# SCH_LoRaRice_Node__2024-06-10.net
KiCad netlist of a schematic drawn in EasyEDA
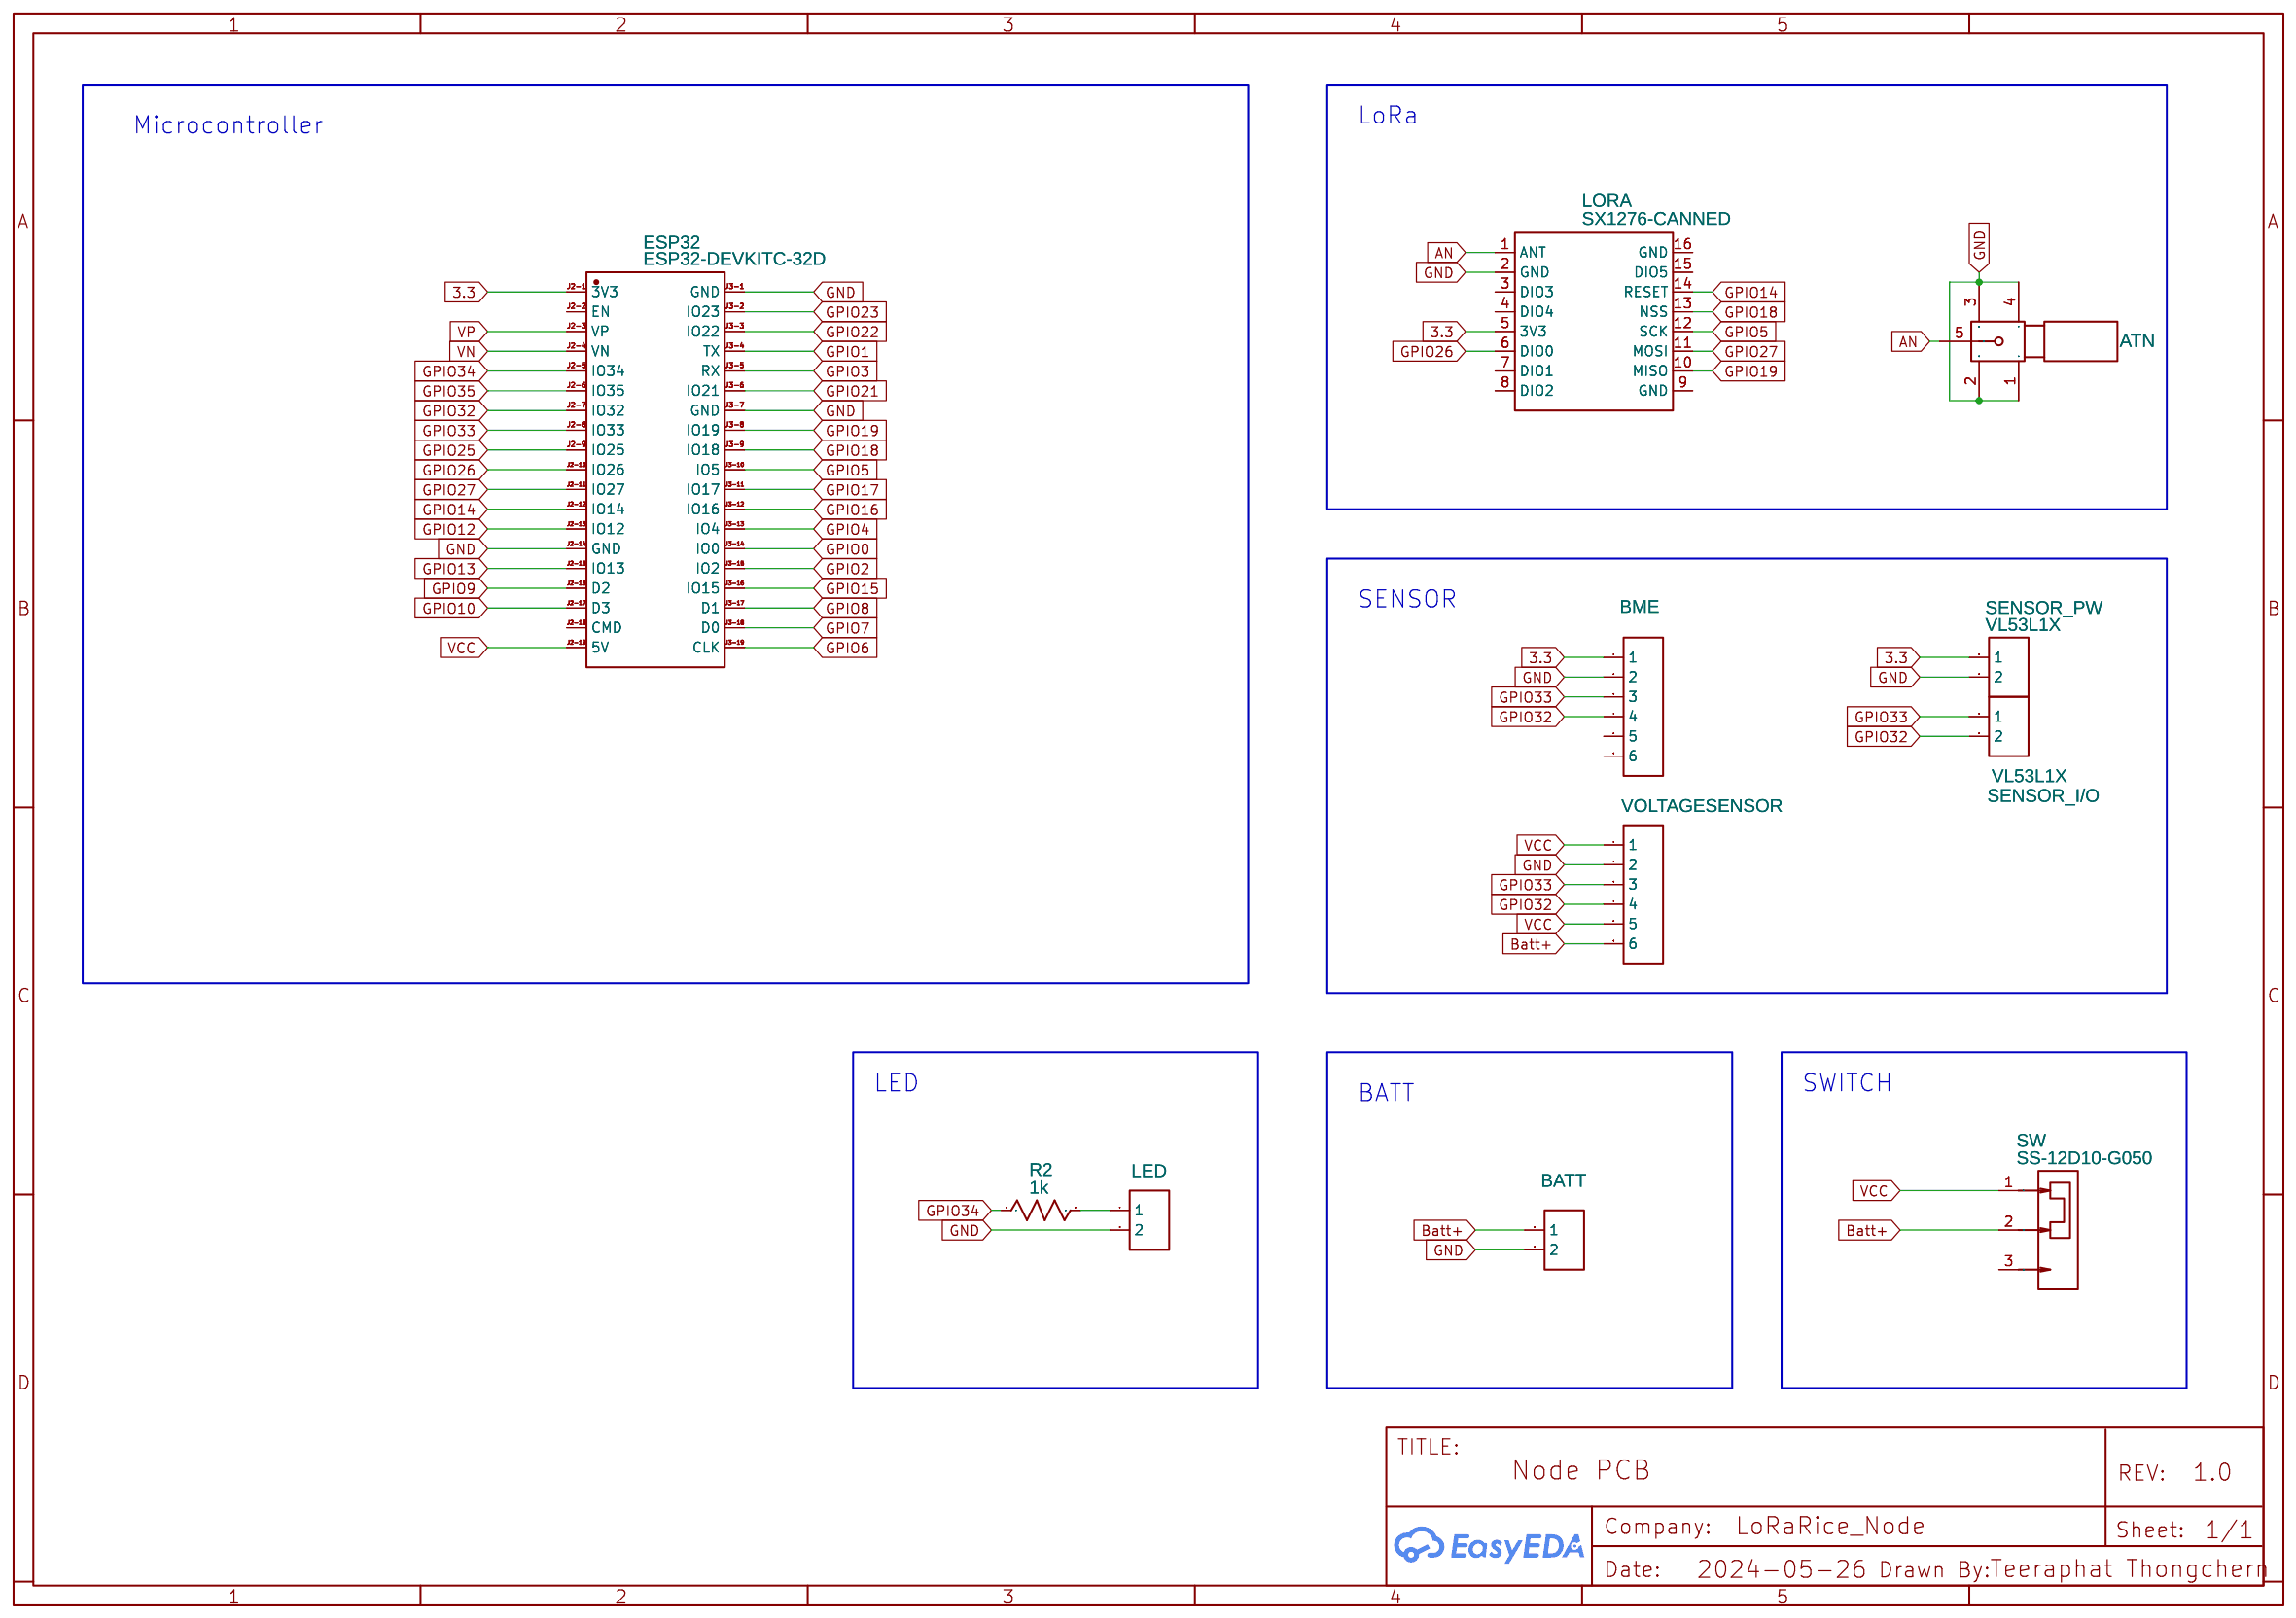
[diagram p0: schematic sheet]

(export (version "E")
  (design (tool "Eeschema 10.0.6"))
  (components
    (comp (ref "ATN")
      (value "ATN")
      (fields
        (field (name "Manufacturer Part") "BWSMA-KE-P001")
        (field (name "Manufacturer") "BAT WIRELESS(蝙蝠无线)")
      )
      (libsource (lib "") (part "BWSMA-KE-P001"))
    )
    (comp (ref "BATT") (value "VL53L1X") (libsource (lib "") (part "CONN-TH_2P-P5.00_1")))
    (comp (ref "BME") (value "00") (libsource (lib "") (part "HDR-F-2.54_1x6_1")))
    (comp (ref "ESP32")
      (value "ESP32-DEVKITC-32D")
      (fields
        (field (name "Manufacturer Part") "ESP32-DevKitC-32D")
        (field (name "Manufacturer") "ESPRESSIF(乐鑫)")
      )
      (libsource (lib "") (part "ESP32-DEVKITC-32D"))
    )
    (comp (ref "LED") (value "HDR-F-2.54_1x2") (libsource (lib "") (part "HDR-F-2.54_1x2")))
    (comp (ref "LORA")
      (value "SX1276-CANNED")
      (fields (field (name "Manufacturer Part") "LoRa1276-C1") (field (name "Manufacturer") "G-NiceRF"))
      (libsource (lib "") (part "SX1276-CANNED"))
    )
    (comp (ref "R2") (value "1k") (libsource (lib "") (part "R_AXIAL-0.4_US")))
    (comp (ref "SENSOR_I/O") (value "VL53L1X") (libsource (lib "") (part "CONN-TH_2P-P5.00")))
    (comp (ref "SENSOR_PW") (value "VL53L1X") (libsource (lib "") (part "CONN-TH_2P-P5.00_2")))
    (comp (ref "SW")
      (value "SS-12D10-G050")
      (fields (field (name "Manufacturer") "G-Switch(品赞)"))
      (libsource (lib "") (part "SS-12D10-G050"))
    )
    (comp (ref "VOLTAGESENSOR") (value "00") (libsource (lib "") (part "HDR-F-2.54_1x6")))
  )
  (nets
    (net (code "1") (name "3.3") (class "Default")
      (node (ref "BME") (pin "1") (pinfunction "1_1") (pintype "input"))
      (node (ref "ESP32") (pin "J2-1") (pinfunction "3V3_J2-1") (pintype "unspecified"))
      (node (ref "LORA") (pin "5") (pinfunction "3V3_5") (pintype "unspecified"))
      (node (ref "SENSOR_PW") (pin "1") (pinfunction "1_1") (pintype "unspecified"))
    )
    (net (code "2") (name "AN") (class "Default")
      (node (ref "ATN") (pin "5") (pinfunction "5_5") (pintype "unspecified"))
      (node (ref "LORA") (pin "1") (pinfunction "ANT_1") (pintype "unspecified"))
    )
    (net (code "3") (name "Batt+") (class "Default")
      (node (ref "BATT") (pin "1") (pinfunction "1_1") (pintype "unspecified"))
      (node (ref "SW") (pin "2") (pinfunction "2_2") (pintype "unspecified"))
      (node (ref "VOLTAGESENSOR") (pin "6") (pinfunction "6_6") (pintype "input"))
    )
    (net (code "4") (name "GND") (class "Default")
      (node (ref "ATN") (pin "1") (pinfunction "1_1") (pintype "unspecified"))
      (node (ref "ATN") (pin "2") (pinfunction "2_2") (pintype "unspecified"))
      (node (ref "ATN") (pin "3") (pinfunction "3_3") (pintype "unspecified"))
      (node (ref "ATN") (pin "4") (pinfunction "4_4") (pintype "unspecified"))
      (node (ref "BATT") (pin "2") (pinfunction "2_2") (pintype "unspecified"))
      (node (ref "BME") (pin "2") (pinfunction "2_2") (pintype "input"))
      (node (ref "ESP32") (pin "J2-14") (pinfunction "GND_J2-14") (pintype "unspecified"))
      (node (ref "ESP32") (pin "J3-1") (pinfunction "GND_J3-1") (pintype "unspecified"))
      (node (ref "ESP32") (pin "J3-7") (pinfunction "GND_J3-7") (pintype "unspecified"))
      (node (ref "LED") (pin "2") (pinfunction "2_2") (pintype "input"))
      (node (ref "LORA") (pin "2") (pinfunction "GND_2") (pintype "unspecified"))
      (node (ref "SENSOR_PW") (pin "2") (pinfunction "2_2") (pintype "unspecified"))
      (node (ref "VOLTAGESENSOR") (pin "2") (pinfunction "2_2") (pintype "input"))
    )
    (net (code "5") (name "GPIO0") (class "Default")
      (node (ref "ESP32") (pin "J3-14") (pinfunction "IO0_J3-14") (pintype "unspecified"))
    )
    (net (code "6") (name "GPIO1") (class "Default")
      (node (ref "ESP32") (pin "J3-4") (pinfunction "TX_J3-4") (pintype "unspecified"))
    )
    (net (code "7") (name "GPIO2") (class "Default")
      (node (ref "ESP32") (pin "J3-15") (pinfunction "IO2_J3-15") (pintype "unspecified"))
    )
    (net (code "8") (name "GPIO3") (class "Default")
      (node (ref "ESP32") (pin "J3-5") (pinfunction "RX_J3-5") (pintype "unspecified"))
    )
    (net (code "9") (name "GPIO4") (class "Default")
      (node (ref "ESP32") (pin "J3-13") (pinfunction "IO4_J3-13") (pintype "unspecified"))
    )
    (net (code "10") (name "GPIO5") (class "Default")
      (node (ref "ESP32") (pin "J3-10") (pinfunction "IO5_J3-10") (pintype "unspecified"))
      (node (ref "LORA") (pin "12") (pinfunction "SCK_12") (pintype "unspecified"))
    )
    (net (code "11") (name "GPIO6") (class "Default")
      (node (ref "ESP32") (pin "J3-19") (pinfunction "CLK_J3-19") (pintype "unspecified"))
    )
    (net (code "12") (name "GPIO7") (class "Default")
      (node (ref "ESP32") (pin "J3-18") (pinfunction "D0_J3-18") (pintype "unspecified"))
    )
    (net (code "13") (name "GPIO8") (class "Default")
      (node (ref "ESP32") (pin "J3-17") (pinfunction "D1_J3-17") (pintype "unspecified"))
    )
    (net (code "14") (name "GPIO9") (class "Default")
      (node (ref "ESP32") (pin "J2-16") (pinfunction "D2_J2-16") (pintype "unspecified"))
    )
    (net (code "15") (name "GPIO10") (class "Default")
      (node (ref "ESP32") (pin "J2-17") (pinfunction "D3_J2-17") (pintype "unspecified"))
    )
    (net (code "16") (name "GPIO12") (class "Default")
      (node (ref "ESP32") (pin "J2-13") (pinfunction "IO12_J2-13") (pintype "unspecified"))
    )
    (net (code "17") (name "GPIO13") (class "Default")
      (node (ref "ESP32") (pin "J2-15") (pinfunction "IO13_J2-15") (pintype "unspecified"))
    )
    (net (code "18") (name "GPIO14") (class "Default")
      (node (ref "ESP32") (pin "J2-12") (pinfunction "IO14_J2-12") (pintype "unspecified"))
      (node (ref "LORA") (pin "14") (pinfunction "RESET_14") (pintype "unspecified"))
    )
    (net (code "19") (name "GPIO15") (class "Default")
      (node (ref "ESP32") (pin "J3-16") (pinfunction "IO15_J3-16") (pintype "unspecified"))
    )
    (net (code "20") (name "GPIO16") (class "Default")
      (node (ref "ESP32") (pin "J3-12") (pinfunction "IO16_J3-12") (pintype "unspecified"))
    )
    (net (code "21") (name "GPIO17") (class "Default")
      (node (ref "ESP32") (pin "J3-11") (pinfunction "IO17_J3-11") (pintype "unspecified"))
    )
    (net (code "22") (name "GPIO18") (class "Default")
      (node (ref "ESP32") (pin "J3-9") (pinfunction "IO18_J3-9") (pintype "unspecified"))
      (node (ref "LORA") (pin "13") (pinfunction "NSS_13") (pintype "unspecified"))
    )
    (net (code "23") (name "GPIO19") (class "Default")
      (node (ref "ESP32") (pin "J3-8") (pinfunction "IO19_J3-8") (pintype "unspecified"))
      (node (ref "LORA") (pin "10") (pinfunction "MISO_10") (pintype "unspecified"))
    )
    (net (code "24") (name "GPIO21") (class "Default")
      (node (ref "ESP32") (pin "J3-6") (pinfunction "IO21_J3-6") (pintype "unspecified"))
    )
    (net (code "25") (name "GPIO22") (class "Default")
      (node (ref "ESP32") (pin "J3-3") (pinfunction "IO22_J3-3") (pintype "unspecified"))
    )
    (net (code "26") (name "GPIO23") (class "Default")
      (node (ref "ESP32") (pin "J3-2") (pinfunction "IO23_J3-2") (pintype "unspecified"))
    )
    (net (code "27") (name "GPIO25") (class "Default")
      (node (ref "ESP32") (pin "J2-9") (pinfunction "IO25_J2-9") (pintype "unspecified"))
    )
    (net (code "28") (name "GPIO26") (class "Default")
      (node (ref "ESP32") (pin "J2-10") (pinfunction "IO26_J2-10") (pintype "unspecified"))
      (node (ref "LORA") (pin "6") (pinfunction "DIO0_6") (pintype "unspecified"))
    )
    (net (code "29") (name "GPIO27") (class "Default")
      (node (ref "ESP32") (pin "J2-11") (pinfunction "IO27_J2-11") (pintype "unspecified"))
      (node (ref "LORA") (pin "11") (pinfunction "MOSI_11") (pintype "unspecified"))
    )
    (net (code "30") (name "GPIO32") (class "Default")
      (node (ref "BME") (pin "4") (pinfunction "4_4") (pintype "input"))
      (node (ref "ESP32") (pin "J2-7") (pinfunction "IO32_J2-7") (pintype "unspecified"))
      (node (ref "SENSOR_I/O") (pin "2") (pinfunction "2_2") (pintype "unspecified"))
      (node (ref "VOLTAGESENSOR") (pin "4") (pinfunction "4_4") (pintype "input"))
    )
    (net (code "31") (name "GPIO33") (class "Default")
      (node (ref "BME") (pin "3") (pinfunction "3_3") (pintype "input"))
      (node (ref "ESP32") (pin "J2-8") (pinfunction "IO33_J2-8") (pintype "unspecified"))
      (node (ref "SENSOR_I/O") (pin "1") (pinfunction "1_1") (pintype "unspecified"))
      (node (ref "VOLTAGESENSOR") (pin "3") (pinfunction "3_3") (pintype "input"))
    )
    (net (code "32") (name "GPIO34") (class "Default")
      (node (ref "ESP32") (pin "J2-5") (pinfunction "IO34_J2-5") (pintype "unspecified"))
      (node (ref "R2") (pin "1") (pinfunction "1_1") (pintype "unspecified"))
    )
    (net (code "33") (name "GPIO35") (class "Default")
      (node (ref "ESP32") (pin "J2-6") (pinfunction "IO35_J2-6") (pintype "unspecified"))
    )
    (net (code "34") (name "Net-(LED-Pad1)") (class "Default")
      (node (ref "LED") (pin "1") (pinfunction "1_1") (pintype "input"))
      (node (ref "R2") (pin "2") (pinfunction "2_2") (pintype "unspecified"))
    )
    (net (code "35") (name "VCC") (class "Default")
      (node (ref "ESP32") (pin "J2-19") (pinfunction "5V_J2-19") (pintype "unspecified"))
      (node (ref "SW") (pin "1") (pinfunction "1_1") (pintype "unspecified"))
      (node (ref "VOLTAGESENSOR") (pin "1") (pinfunction "1_1") (pintype "input"))
      (node (ref "VOLTAGESENSOR") (pin "5") (pinfunction "5_5") (pintype "input"))
    )
    (net (code "36") (name "VN") (class "Default")
      (node (ref "ESP32") (pin "J2-4") (pinfunction "VN_J2-4") (pintype "unspecified"))
    )
    (net (code "37") (name "VP") (class "Default")
      (node (ref "ESP32") (pin "J2-3") (pinfunction "VP_J2-3") (pintype "unspecified"))
    )
    (net (code "38") (name "unconnected-(BME-Pad5)") (class "Default")
      (node (ref "BME") (pin "5") (pinfunction "5_5") (pintype "input"))
    )
    (net (code "39") (name "unconnected-(BME-Pad6)") (class "Default")
      (node (ref "BME") (pin "6") (pinfunction "6_6") (pintype "input"))
    )
    (net (code "40") (name "unconnected-(ESP32-CMD-PadJ2-18)") (class "Default")
      (node (ref "ESP32") (pin "J2-18") (pinfunction "CMD_J2-18") (pintype "unspecified"))
    )
    (net (code "41") (name "unconnected-(ESP32-EN-PadJ2-2)") (class "Default")
      (node (ref "ESP32") (pin "J2-2") (pinfunction "EN_J2-2") (pintype "unspecified"))
    )
    (net (code "42") (name "unconnected-(LORA-DIO1-Pad7)") (class "Default")
      (node (ref "LORA") (pin "7") (pinfunction "DIO1_7") (pintype "unspecified"))
    )
    (net (code "43") (name "unconnected-(LORA-DIO2-Pad8)") (class "Default")
      (node (ref "LORA") (pin "8") (pinfunction "DIO2_8") (pintype "unspecified"))
    )
    (net (code "44") (name "unconnected-(LORA-DIO3-Pad3)") (class "Default")
      (node (ref "LORA") (pin "3") (pinfunction "DIO3_3") (pintype "unspecified"))
    )
    (net (code "45") (name "unconnected-(LORA-DIO4-Pad4)") (class "Default")
      (node (ref "LORA") (pin "4") (pinfunction "DIO4_4") (pintype "unspecified"))
    )
    (net (code "46") (name "unconnected-(LORA-DIO5-Pad15)") (class "Default")
      (node (ref "LORA") (pin "15") (pinfunction "DIO5_15") (pintype "unspecified"))
    )
    (net (code "47") (name "unconnected-(LORA-GND-Pad9)") (class "Default")
      (node (ref "LORA") (pin "9") (pinfunction "GND_9") (pintype "unspecified"))
    )
    (net (code "48") (name "unconnected-(LORA-GND-Pad16)") (class "Default")
      (node (ref "LORA") (pin "16") (pinfunction "GND_16") (pintype "unspecified"))
    )
    (net (code "49") (name "unconnected-(SW-Pad3)") (class "Default")
      (node (ref "SW") (pin "3") (pinfunction "3_3") (pintype "unspecified"))
    )
  )
)
